# Square.net
KiCad netlist of a schematic drawn in Altium Designer
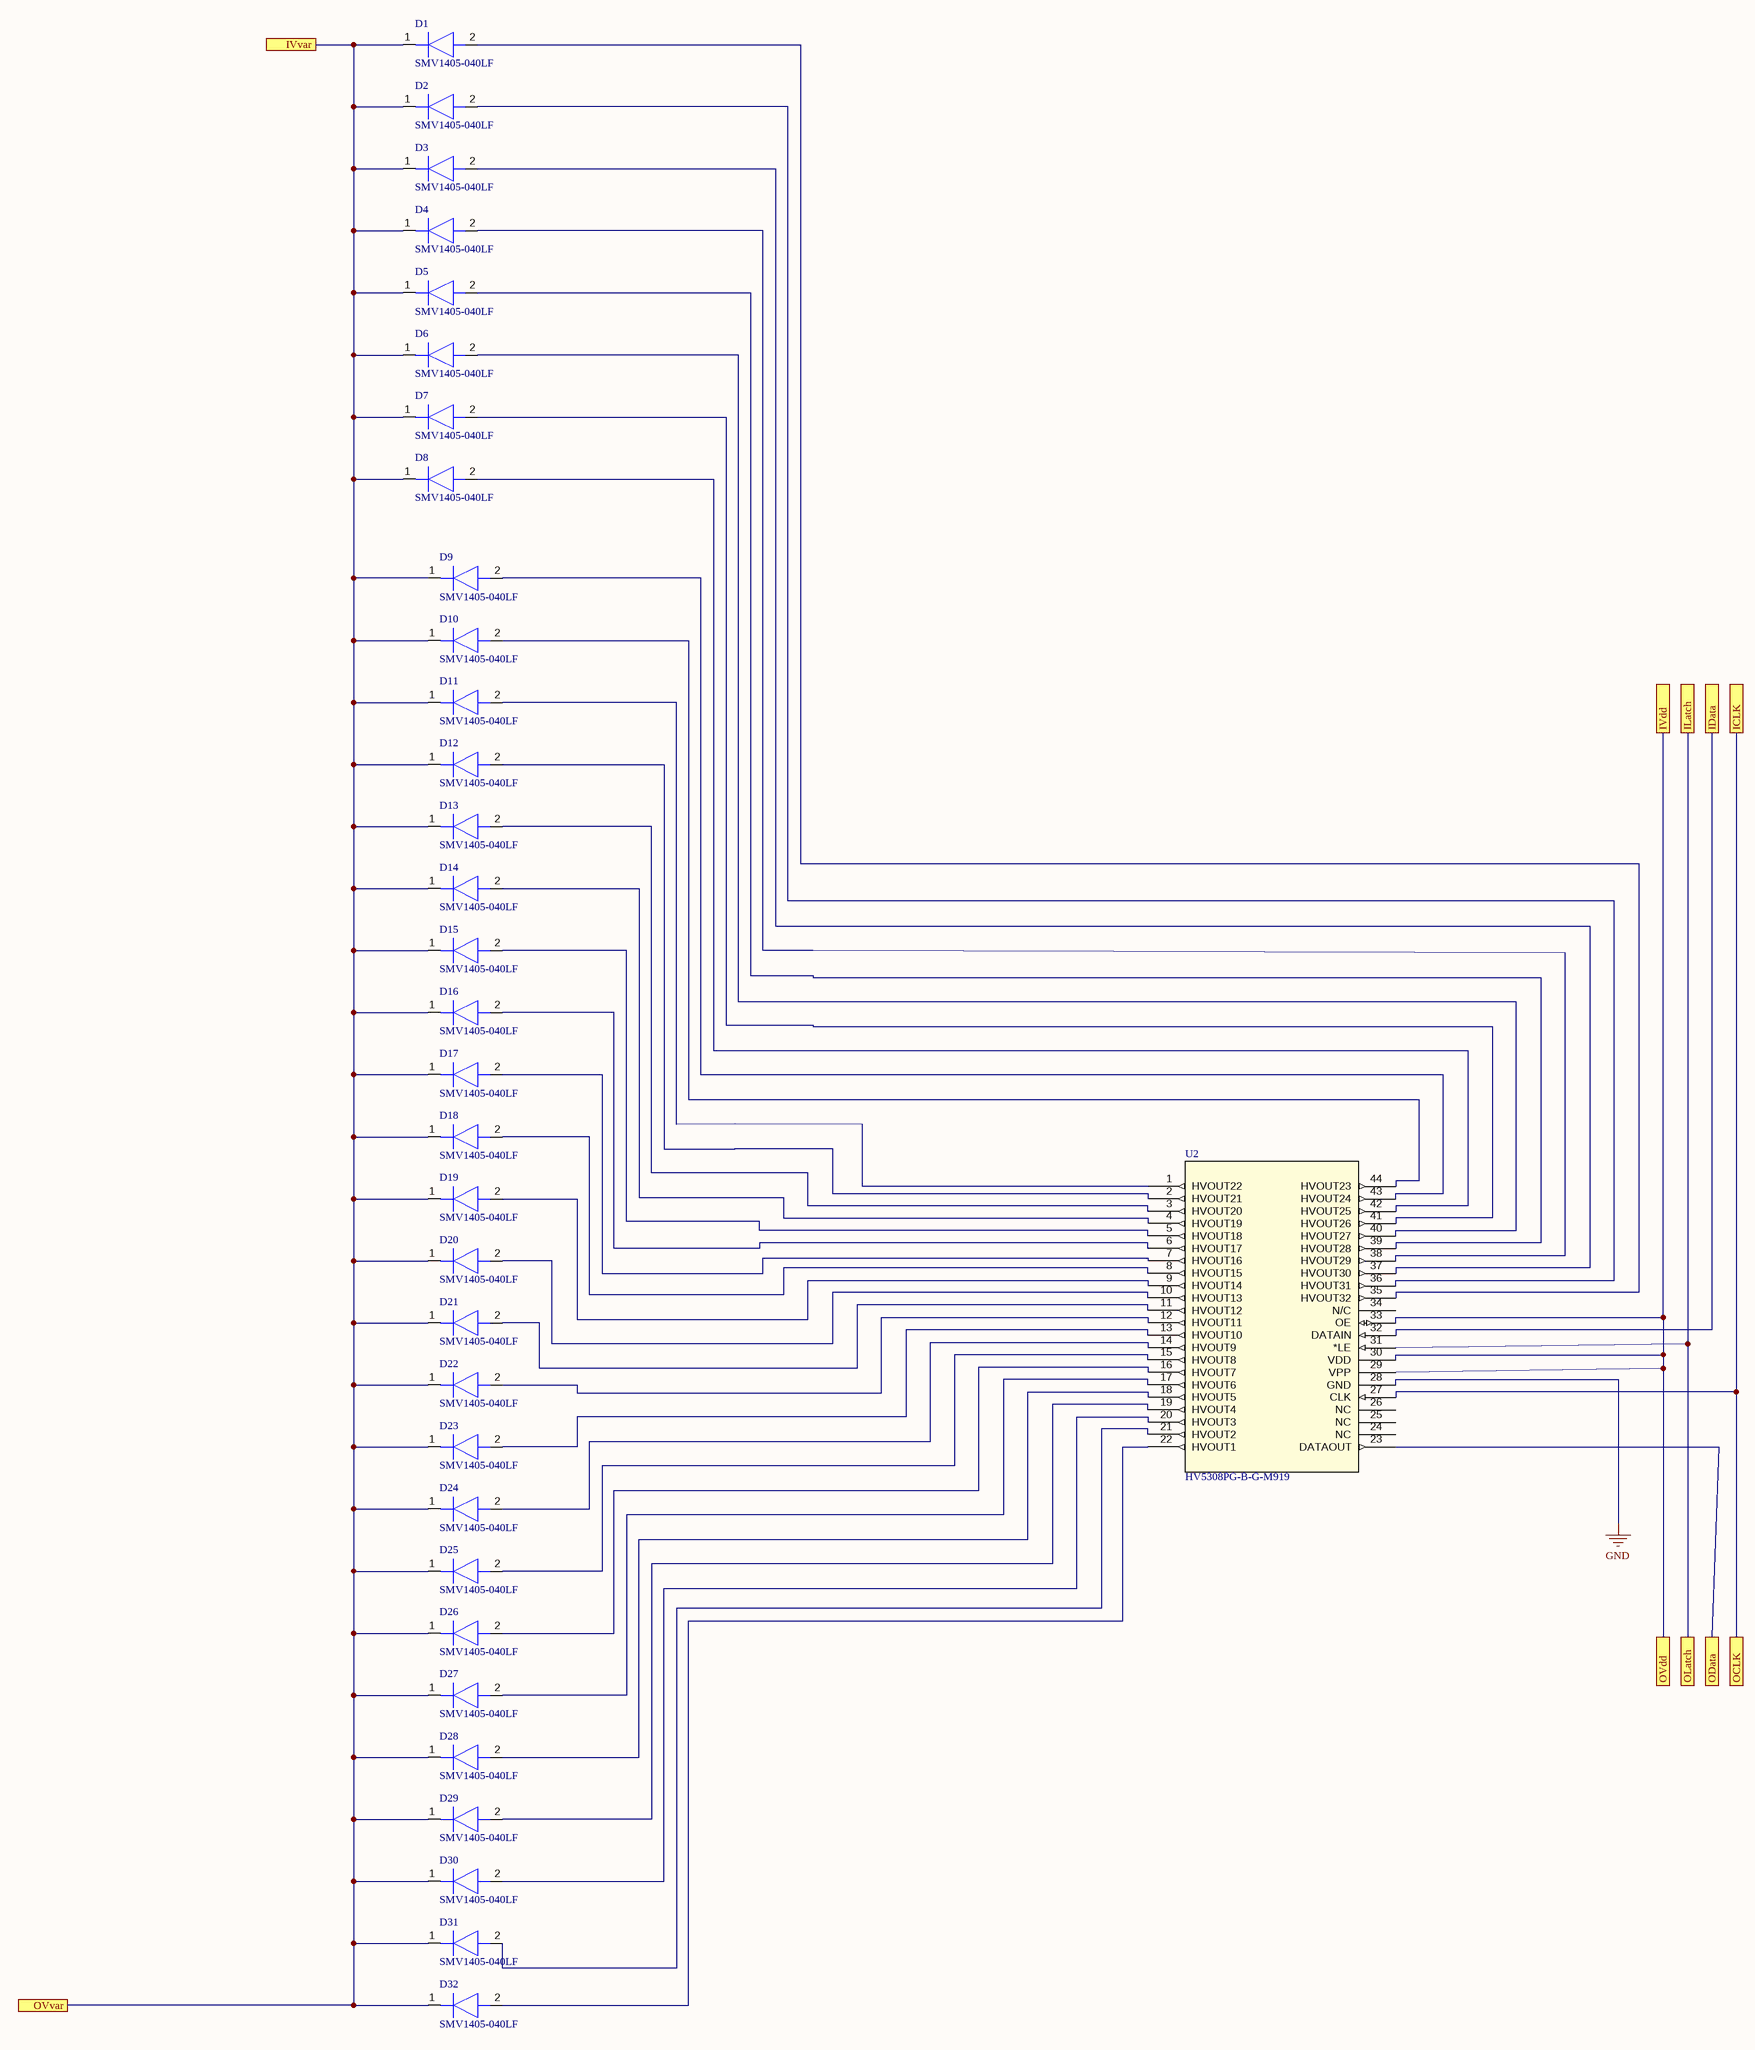
[diagram p0: Square.SchDoc]

(export (version "E")
  (design (tool "Eeschema 10.0.6"))
  (components
    (comp (ref "D1")
      (value "SMV1405-040LF")
      (footprint "SamacSys:SMV1405040LF")
      (description "Diode")
      (fields (field (name "MOUSER PART NUMBER") "873-SMV1405-040LF"))
      (libsource (lib "SamacSys") (part "SMV1405-040LF"))
    )
    (comp (ref "D2")
      (value "SMV1405-040LF")
      (footprint "SamacSys:SMV1405040LF")
      (description "Diode")
      (fields (field (name "MOUSER PART NUMBER") "873-SMV1405-040LF"))
      (libsource (lib "SamacSys") (part "SMV1405-040LF"))
    )
    (comp (ref "D3")
      (value "SMV1405-040LF")
      (footprint "SamacSys:SMV1405040LF")
      (description "Diode")
      (fields (field (name "MOUSER PART NUMBER") "873-SMV1405-040LF"))
      (libsource (lib "SamacSys") (part "SMV1405-040LF"))
    )
    (comp (ref "D4")
      (value "SMV1405-040LF")
      (footprint "SamacSys:SMV1405040LF")
      (description "Diode")
      (fields (field (name "MOUSER PART NUMBER") "873-SMV1405-040LF"))
      (libsource (lib "SamacSys") (part "SMV1405-040LF"))
    )
    (comp (ref "D5")
      (value "SMV1405-040LF")
      (footprint "SamacSys:SMV1405040LF")
      (description "Diode")
      (fields (field (name "MOUSER PART NUMBER") "873-SMV1405-040LF"))
      (libsource (lib "SamacSys") (part "SMV1405-040LF"))
    )
    (comp (ref "D6")
      (value "SMV1405-040LF")
      (footprint "SamacSys:SMV1405040LF")
      (description "Diode")
      (fields (field (name "MOUSER PART NUMBER") "873-SMV1405-040LF"))
      (libsource (lib "SamacSys") (part "SMV1405-040LF"))
    )
    (comp (ref "D7")
      (value "SMV1405-040LF")
      (footprint "SamacSys:SMV1405040LF")
      (description "Diode")
      (fields (field (name "MOUSER PART NUMBER") "873-SMV1405-040LF"))
      (libsource (lib "SamacSys") (part "SMV1405-040LF"))
    )
    (comp (ref "D8")
      (value "SMV1405-040LF")
      (footprint "SamacSys:SMV1405040LF")
      (description "Diode")
      (fields (field (name "MOUSER PART NUMBER") "873-SMV1405-040LF"))
      (libsource (lib "SamacSys") (part "SMV1405-040LF"))
    )
    (comp (ref "D9")
      (value "SMV1405-040LF")
      (footprint "SamacSys:SMV1405040LF")
      (description "Diode")
      (fields (field (name "MOUSER PART NUMBER") "873-SMV1405-040LF"))
      (libsource (lib "SamacSys") (part "SMV1405-040LF"))
    )
    (comp (ref "D10")
      (value "SMV1405-040LF")
      (footprint "SamacSys:SMV1405040LF")
      (description "Diode")
      (fields (field (name "MOUSER PART NUMBER") "873-SMV1405-040LF"))
      (libsource (lib "SamacSys") (part "SMV1405-040LF"))
    )
    (comp (ref "D11")
      (value "SMV1405-040LF")
      (footprint "SamacSys:SMV1405040LF")
      (description "Diode")
      (fields (field (name "MOUSER PART NUMBER") "873-SMV1405-040LF"))
      (libsource (lib "SamacSys") (part "SMV1405-040LF"))
    )
    (comp (ref "D12")
      (value "SMV1405-040LF")
      (footprint "SamacSys:SMV1405040LF")
      (description "Diode")
      (fields (field (name "MOUSER PART NUMBER") "873-SMV1405-040LF"))
      (libsource (lib "SamacSys") (part "SMV1405-040LF"))
    )
    (comp (ref "D13")
      (value "SMV1405-040LF")
      (footprint "SamacSys:SMV1405040LF")
      (description "Diode")
      (fields (field (name "MOUSER PART NUMBER") "873-SMV1405-040LF"))
      (libsource (lib "SamacSys") (part "SMV1405-040LF"))
    )
    (comp (ref "D14")
      (value "SMV1405-040LF")
      (footprint "SamacSys:SMV1405040LF")
      (description "Diode")
      (fields (field (name "MOUSER PART NUMBER") "873-SMV1405-040LF"))
      (libsource (lib "SamacSys") (part "SMV1405-040LF"))
    )
    (comp (ref "D15")
      (value "SMV1405-040LF")
      (footprint "SamacSys:SMV1405040LF")
      (description "Diode")
      (fields (field (name "MOUSER PART NUMBER") "873-SMV1405-040LF"))
      (libsource (lib "SamacSys") (part "SMV1405-040LF"))
    )
    (comp (ref "D16")
      (value "SMV1405-040LF")
      (footprint "SamacSys:SMV1405040LF")
      (description "Diode")
      (fields (field (name "MOUSER PART NUMBER") "873-SMV1405-040LF"))
      (libsource (lib "SamacSys") (part "SMV1405-040LF"))
    )
    (comp (ref "D17")
      (value "SMV1405-040LF")
      (footprint "SamacSys:SMV1405040LF")
      (description "Diode")
      (fields (field (name "MOUSER PART NUMBER") "873-SMV1405-040LF"))
      (libsource (lib "SamacSys") (part "SMV1405-040LF"))
    )
    (comp (ref "D18")
      (value "SMV1405-040LF")
      (footprint "SamacSys:SMV1405040LF")
      (description "Diode")
      (fields (field (name "MOUSER PART NUMBER") "873-SMV1405-040LF"))
      (libsource (lib "SamacSys") (part "SMV1405-040LF"))
    )
    (comp (ref "D19")
      (value "SMV1405-040LF")
      (footprint "SamacSys:SMV1405040LF")
      (description "Diode")
      (fields (field (name "MOUSER PART NUMBER") "873-SMV1405-040LF"))
      (libsource (lib "SamacSys") (part "SMV1405-040LF"))
    )
    (comp (ref "D20")
      (value "SMV1405-040LF")
      (footprint "SamacSys:SMV1405040LF")
      (description "Diode")
      (fields (field (name "MOUSER PART NUMBER") "873-SMV1405-040LF"))
      (libsource (lib "SamacSys") (part "SMV1405-040LF"))
    )
    (comp (ref "D21")
      (value "SMV1405-040LF")
      (footprint "SamacSys:SMV1405040LF")
      (description "Diode")
      (fields (field (name "MOUSER PART NUMBER") "873-SMV1405-040LF"))
      (libsource (lib "SamacSys") (part "SMV1405-040LF"))
    )
    (comp (ref "D22")
      (value "SMV1405-040LF")
      (footprint "SamacSys:SMV1405040LF")
      (description "Diode")
      (fields (field (name "MOUSER PART NUMBER") "873-SMV1405-040LF"))
      (libsource (lib "SamacSys") (part "SMV1405-040LF"))
    )
    (comp (ref "D23")
      (value "SMV1405-040LF")
      (footprint "SamacSys:SMV1405040LF")
      (description "Diode")
      (fields (field (name "MOUSER PART NUMBER") "873-SMV1405-040LF"))
      (libsource (lib "SamacSys") (part "SMV1405-040LF"))
    )
    (comp (ref "D24")
      (value "SMV1405-040LF")
      (footprint "SamacSys:SMV1405040LF")
      (description "Diode")
      (fields (field (name "MOUSER PART NUMBER") "873-SMV1405-040LF"))
      (libsource (lib "SamacSys") (part "SMV1405-040LF"))
    )
    (comp (ref "D25")
      (value "SMV1405-040LF")
      (footprint "SamacSys:SMV1405040LF")
      (description "Diode")
      (fields (field (name "MOUSER PART NUMBER") "873-SMV1405-040LF"))
      (libsource (lib "SamacSys") (part "SMV1405-040LF"))
    )
    (comp (ref "D26")
      (value "SMV1405-040LF")
      (footprint "SamacSys:SMV1405040LF")
      (description "Diode")
      (fields (field (name "MOUSER PART NUMBER") "873-SMV1405-040LF"))
      (libsource (lib "SamacSys") (part "SMV1405-040LF"))
    )
    (comp (ref "D27")
      (value "SMV1405-040LF")
      (footprint "SamacSys:SMV1405040LF")
      (description "Diode")
      (fields (field (name "MOUSER PART NUMBER") "873-SMV1405-040LF"))
      (libsource (lib "SamacSys") (part "SMV1405-040LF"))
    )
    (comp (ref "D28")
      (value "SMV1405-040LF")
      (footprint "SamacSys:SMV1405040LF")
      (description "Diode")
      (fields (field (name "MOUSER PART NUMBER") "873-SMV1405-040LF"))
      (libsource (lib "SamacSys") (part "SMV1405-040LF"))
    )
    (comp (ref "D29")
      (value "SMV1405-040LF")
      (footprint "SamacSys:SMV1405040LF")
      (description "Diode")
      (fields (field (name "MOUSER PART NUMBER") "873-SMV1405-040LF"))
      (libsource (lib "SamacSys") (part "SMV1405-040LF"))
    )
    (comp (ref "D30")
      (value "SMV1405-040LF")
      (footprint "SamacSys:SMV1405040LF")
      (description "Diode")
      (fields (field (name "MOUSER PART NUMBER") "873-SMV1405-040LF"))
      (libsource (lib "SamacSys") (part "SMV1405-040LF"))
    )
    (comp (ref "D31")
      (value "SMV1405-040LF")
      (footprint "SamacSys:SMV1405040LF")
      (description "Diode")
      (fields (field (name "MOUSER PART NUMBER") "873-SMV1405-040LF"))
      (libsource (lib "SamacSys") (part "SMV1405-040LF"))
    )
    (comp (ref "D32")
      (value "SMV1405-040LF")
      (footprint "SamacSys:SMV1405040LF")
      (description "Diode")
      (fields (field (name "MOUSER PART NUMBER") "873-SMV1405-040LF"))
      (libsource (lib "SamacSys") (part "SMV1405-040LF"))
    )
    (comp (ref "U2")
      (value "HV5308PG-B-G-M919")
      (footprint "QFP44_10x10MC_MCH")
      (description "No Description Available")
      (fields (field (name "COPYRIGHT") "Copyright (C) 2022 Ultra Librarian. All rights reserved."))
      (libsource (lib "HV5308PG-B-G-M919") (part "HV5308PG-B-G-M919"))
    )
  )
  (nets
    (net (code "1") (name "/ICLK") (class "Default")
      (node (ref "U2") (pin "27") (pinfunction "CLK_27") (pintype "input"))
    )
    (net (code "2") (name "/IData") (class "Default")
      (node (ref "U2") (pin "32") (pinfunction "DATAIN_32") (pintype "input"))
    )
    (net (code "3") (name "/ILatch") (class "Default")
      (node (ref "U2") (pin "31") (pinfunction "*LE_31") (pintype "input"))
    )
    (net (code "4") (name "/IVdd") (class "Default")
      (node (ref "U2") (pin "29") (pinfunction "VPP_29") (pintype "power_in"))
      (node (ref "U2") (pin "30") (pinfunction "VDD_30") (pintype "power_in"))
      (node (ref "U2") (pin "33") (pinfunction "OE_33") (pintype "bidirectional"))
    )
    (net (code "5") (name "/IVvar") (class "Default")
      (node (ref "D1") (pin "1") (pinfunction "K_1") (pintype "passive"))
      (node (ref "D10") (pin "1") (pinfunction "K_1") (pintype "passive"))
      (node (ref "D11") (pin "1") (pinfunction "K_1") (pintype "passive"))
      (node (ref "D12") (pin "1") (pinfunction "K_1") (pintype "passive"))
      (node (ref "D13") (pin "1") (pinfunction "K_1") (pintype "passive"))
      (node (ref "D14") (pin "1") (pinfunction "K_1") (pintype "passive"))
      (node (ref "D15") (pin "1") (pinfunction "K_1") (pintype "passive"))
      (node (ref "D16") (pin "1") (pinfunction "K_1") (pintype "passive"))
      (node (ref "D17") (pin "1") (pinfunction "K_1") (pintype "passive"))
      (node (ref "D18") (pin "1") (pinfunction "K_1") (pintype "passive"))
      (node (ref "D19") (pin "1") (pinfunction "K_1") (pintype "passive"))
      (node (ref "D2") (pin "1") (pinfunction "K_1") (pintype "passive"))
      (node (ref "D20") (pin "1") (pinfunction "K_1") (pintype "passive"))
      (node (ref "D21") (pin "1") (pinfunction "K_1") (pintype "passive"))
      (node (ref "D22") (pin "1") (pinfunction "K_1") (pintype "passive"))
      (node (ref "D23") (pin "1") (pinfunction "K_1") (pintype "passive"))
      (node (ref "D24") (pin "1") (pinfunction "K_1") (pintype "passive"))
      (node (ref "D25") (pin "1") (pinfunction "K_1") (pintype "passive"))
      (node (ref "D26") (pin "1") (pinfunction "K_1") (pintype "passive"))
      (node (ref "D27") (pin "1") (pinfunction "K_1") (pintype "passive"))
      (node (ref "D28") (pin "1") (pinfunction "K_1") (pintype "passive"))
      (node (ref "D29") (pin "1") (pinfunction "K_1") (pintype "passive"))
      (node (ref "D3") (pin "1") (pinfunction "K_1") (pintype "passive"))
      (node (ref "D30") (pin "1") (pinfunction "K_1") (pintype "passive"))
      (node (ref "D31") (pin "1") (pinfunction "K_1") (pintype "passive"))
      (node (ref "D32") (pin "1") (pinfunction "K_1") (pintype "passive"))
      (node (ref "D4") (pin "1") (pinfunction "K_1") (pintype "passive"))
      (node (ref "D5") (pin "1") (pinfunction "K_1") (pintype "passive"))
      (node (ref "D6") (pin "1") (pinfunction "K_1") (pintype "passive"))
      (node (ref "D7") (pin "1") (pinfunction "K_1") (pintype "passive"))
      (node (ref "D8") (pin "1") (pinfunction "K_1") (pintype "passive"))
      (node (ref "D9") (pin "1") (pinfunction "K_1") (pintype "passive"))
    )
    (net (code "6") (name "/OData") (class "Default")
      (node (ref "U2") (pin "23") (pinfunction "DATAOUT_23") (pintype "output"))
    )
    (net (code "7") (name "GND") (class "Default")
      (node (ref "U2") (pin "28") (pinfunction "GND_28") (pintype "passive"))
    )
    (net (code "8") (name "Net-(D1-A)") (class "Default")
      (node (ref "D1") (pin "2") (pinfunction "A_2") (pintype "passive"))
      (node (ref "U2") (pin "35") (pinfunction "HVOUT32_35") (pintype "output"))
    )
    (net (code "9") (name "Net-(D2-A)") (class "Default")
      (node (ref "D2") (pin "2") (pinfunction "A_2") (pintype "passive"))
      (node (ref "U2") (pin "36") (pinfunction "HVOUT31_36") (pintype "output"))
    )
    (net (code "10") (name "Net-(D3-A)") (class "Default")
      (node (ref "D3") (pin "2") (pinfunction "A_2") (pintype "passive"))
      (node (ref "U2") (pin "37") (pinfunction "HVOUT30_37") (pintype "output"))
    )
    (net (code "11") (name "Net-(D4-A)") (class "Default")
      (node (ref "D4") (pin "2") (pinfunction "A_2") (pintype "passive"))
      (node (ref "U2") (pin "38") (pinfunction "HVOUT29_38") (pintype "output"))
    )
    (net (code "12") (name "Net-(D5-A)") (class "Default")
      (node (ref "D5") (pin "2") (pinfunction "A_2") (pintype "passive"))
      (node (ref "U2") (pin "39") (pinfunction "HVOUT28_39") (pintype "output"))
    )
    (net (code "13") (name "Net-(D6-A)") (class "Default")
      (node (ref "D6") (pin "2") (pinfunction "A_2") (pintype "passive"))
      (node (ref "U2") (pin "40") (pinfunction "HVOUT27_40") (pintype "output"))
    )
    (net (code "14") (name "Net-(D7-A)") (class "Default")
      (node (ref "D7") (pin "2") (pinfunction "A_2") (pintype "passive"))
      (node (ref "U2") (pin "41") (pinfunction "HVOUT26_41") (pintype "output"))
    )
    (net (code "15") (name "Net-(D8-A)") (class "Default")
      (node (ref "D8") (pin "2") (pinfunction "A_2") (pintype "passive"))
      (node (ref "U2") (pin "42") (pinfunction "HVOUT25_42") (pintype "output"))
    )
    (net (code "16") (name "Net-(D9-A)") (class "Default")
      (node (ref "D9") (pin "2") (pinfunction "A_2") (pintype "passive"))
      (node (ref "U2") (pin "43") (pinfunction "HVOUT24_43") (pintype "output"))
    )
    (net (code "17") (name "Net-(D10-A)") (class "Default")
      (node (ref "D10") (pin "2") (pinfunction "A_2") (pintype "passive"))
      (node (ref "U2") (pin "44") (pinfunction "HVOUT23_44") (pintype "output"))
    )
    (net (code "18") (name "Net-(D11-A)") (class "Default")
      (node (ref "D11") (pin "2") (pinfunction "A_2") (pintype "passive"))
      (node (ref "U2") (pin "1") (pinfunction "HVOUT22_1") (pintype "output"))
    )
    (net (code "19") (name "Net-(D12-A)") (class "Default")
      (node (ref "D12") (pin "2") (pinfunction "A_2") (pintype "passive"))
      (node (ref "U2") (pin "2") (pinfunction "HVOUT21_2") (pintype "output"))
    )
    (net (code "20") (name "Net-(D13-A)") (class "Default")
      (node (ref "D13") (pin "2") (pinfunction "A_2") (pintype "passive"))
      (node (ref "U2") (pin "3") (pinfunction "HVOUT20_3") (pintype "output"))
    )
    (net (code "21") (name "Net-(D14-A)") (class "Default")
      (node (ref "D14") (pin "2") (pinfunction "A_2") (pintype "passive"))
      (node (ref "U2") (pin "4") (pinfunction "HVOUT19_4") (pintype "output"))
    )
    (net (code "22") (name "Net-(D15-A)") (class "Default")
      (node (ref "D15") (pin "2") (pinfunction "A_2") (pintype "passive"))
      (node (ref "U2") (pin "5") (pinfunction "HVOUT18_5") (pintype "output"))
    )
    (net (code "23") (name "Net-(D16-A)") (class "Default")
      (node (ref "D16") (pin "2") (pinfunction "A_2") (pintype "passive"))
      (node (ref "U2") (pin "6") (pinfunction "HVOUT17_6") (pintype "output"))
    )
    (net (code "24") (name "Net-(D17-A)") (class "Default")
      (node (ref "D17") (pin "2") (pinfunction "A_2") (pintype "passive"))
      (node (ref "U2") (pin "7") (pinfunction "HVOUT16_7") (pintype "output"))
    )
    (net (code "25") (name "Net-(D18-A)") (class "Default")
      (node (ref "D18") (pin "2") (pinfunction "A_2") (pintype "passive"))
      (node (ref "U2") (pin "8") (pinfunction "HVOUT15_8") (pintype "output"))
    )
    (net (code "26") (name "Net-(D19-A)") (class "Default")
      (node (ref "D19") (pin "2") (pinfunction "A_2") (pintype "passive"))
      (node (ref "U2") (pin "9") (pinfunction "HVOUT14_9") (pintype "output"))
    )
    (net (code "27") (name "Net-(D20-A)") (class "Default")
      (node (ref "D20") (pin "2") (pinfunction "A_2") (pintype "passive"))
      (node (ref "U2") (pin "10") (pinfunction "HVOUT13_10") (pintype "output"))
    )
    (net (code "28") (name "Net-(D21-A)") (class "Default")
      (node (ref "D21") (pin "2") (pinfunction "A_2") (pintype "passive"))
      (node (ref "U2") (pin "11") (pinfunction "HVOUT12_11") (pintype "output"))
    )
    (net (code "29") (name "Net-(D22-A)") (class "Default")
      (node (ref "D22") (pin "2") (pinfunction "A_2") (pintype "passive"))
      (node (ref "U2") (pin "12") (pinfunction "HVOUT11_12") (pintype "output"))
    )
    (net (code "30") (name "Net-(D23-A)") (class "Default")
      (node (ref "D23") (pin "2") (pinfunction "A_2") (pintype "passive"))
      (node (ref "U2") (pin "13") (pinfunction "HVOUT10_13") (pintype "output"))
    )
    (net (code "31") (name "Net-(D24-A)") (class "Default")
      (node (ref "D24") (pin "2") (pinfunction "A_2") (pintype "passive"))
      (node (ref "U2") (pin "14") (pinfunction "HVOUT9_14") (pintype "output"))
    )
    (net (code "32") (name "Net-(D25-A)") (class "Default")
      (node (ref "D25") (pin "2") (pinfunction "A_2") (pintype "passive"))
      (node (ref "U2") (pin "15") (pinfunction "HVOUT8_15") (pintype "output"))
    )
    (net (code "33") (name "Net-(D26-A)") (class "Default")
      (node (ref "D26") (pin "2") (pinfunction "A_2") (pintype "passive"))
      (node (ref "U2") (pin "16") (pinfunction "HVOUT7_16") (pintype "output"))
    )
    (net (code "34") (name "Net-(D27-A)") (class "Default")
      (node (ref "D27") (pin "2") (pinfunction "A_2") (pintype "passive"))
      (node (ref "U2") (pin "17") (pinfunction "HVOUT6_17") (pintype "output"))
    )
    (net (code "35") (name "Net-(D28-A)") (class "Default")
      (node (ref "D28") (pin "2") (pinfunction "A_2") (pintype "passive"))
      (node (ref "U2") (pin "18") (pinfunction "HVOUT5_18") (pintype "output"))
    )
    (net (code "36") (name "Net-(D29-A)") (class "Default")
      (node (ref "D29") (pin "2") (pinfunction "A_2") (pintype "passive"))
      (node (ref "U2") (pin "19") (pinfunction "HVOUT4_19") (pintype "output"))
    )
    (net (code "37") (name "Net-(D30-A)") (class "Default")
      (node (ref "D30") (pin "2") (pinfunction "A_2") (pintype "passive"))
      (node (ref "U2") (pin "20") (pinfunction "HVOUT3_20") (pintype "output"))
    )
    (net (code "38") (name "Net-(D31-A)") (class "Default")
      (node (ref "D31") (pin "2") (pinfunction "A_2") (pintype "passive"))
      (node (ref "U2") (pin "21") (pinfunction "HVOUT2_21") (pintype "output"))
    )
    (net (code "39") (name "Net-(D32-A)") (class "Default")
      (node (ref "D32") (pin "2") (pinfunction "A_2") (pintype "passive"))
      (node (ref "U2") (pin "22") (pinfunction "HVOUT1_22") (pintype "output"))
    )
    (net (code "40") (name "unconnected-(U2-NC-Pad24)") (class "Default")
      (node (ref "U2") (pin "24") (pinfunction "NC_24") (pintype "passive"))
    )
    (net (code "41") (name "unconnected-(U2-NC-Pad25)") (class "Default")
      (node (ref "U2") (pin "25") (pinfunction "NC_25") (pintype "passive"))
    )
    (net (code "42") (name "unconnected-(U2-NC-Pad26)") (class "Default")
      (node (ref "U2") (pin "26") (pinfunction "NC_26") (pintype "passive"))
    )
    (net (code "43") (name "unconnected-(U2-N{slash}C-Pad34)") (class "Default")
      (node (ref "U2") (pin "34") (pinfunction "N/C_34") (pintype "passive"))
    )
  )
)
